# auto_gardener.net
KiCad netlist of a schematic drawn in EAGLE
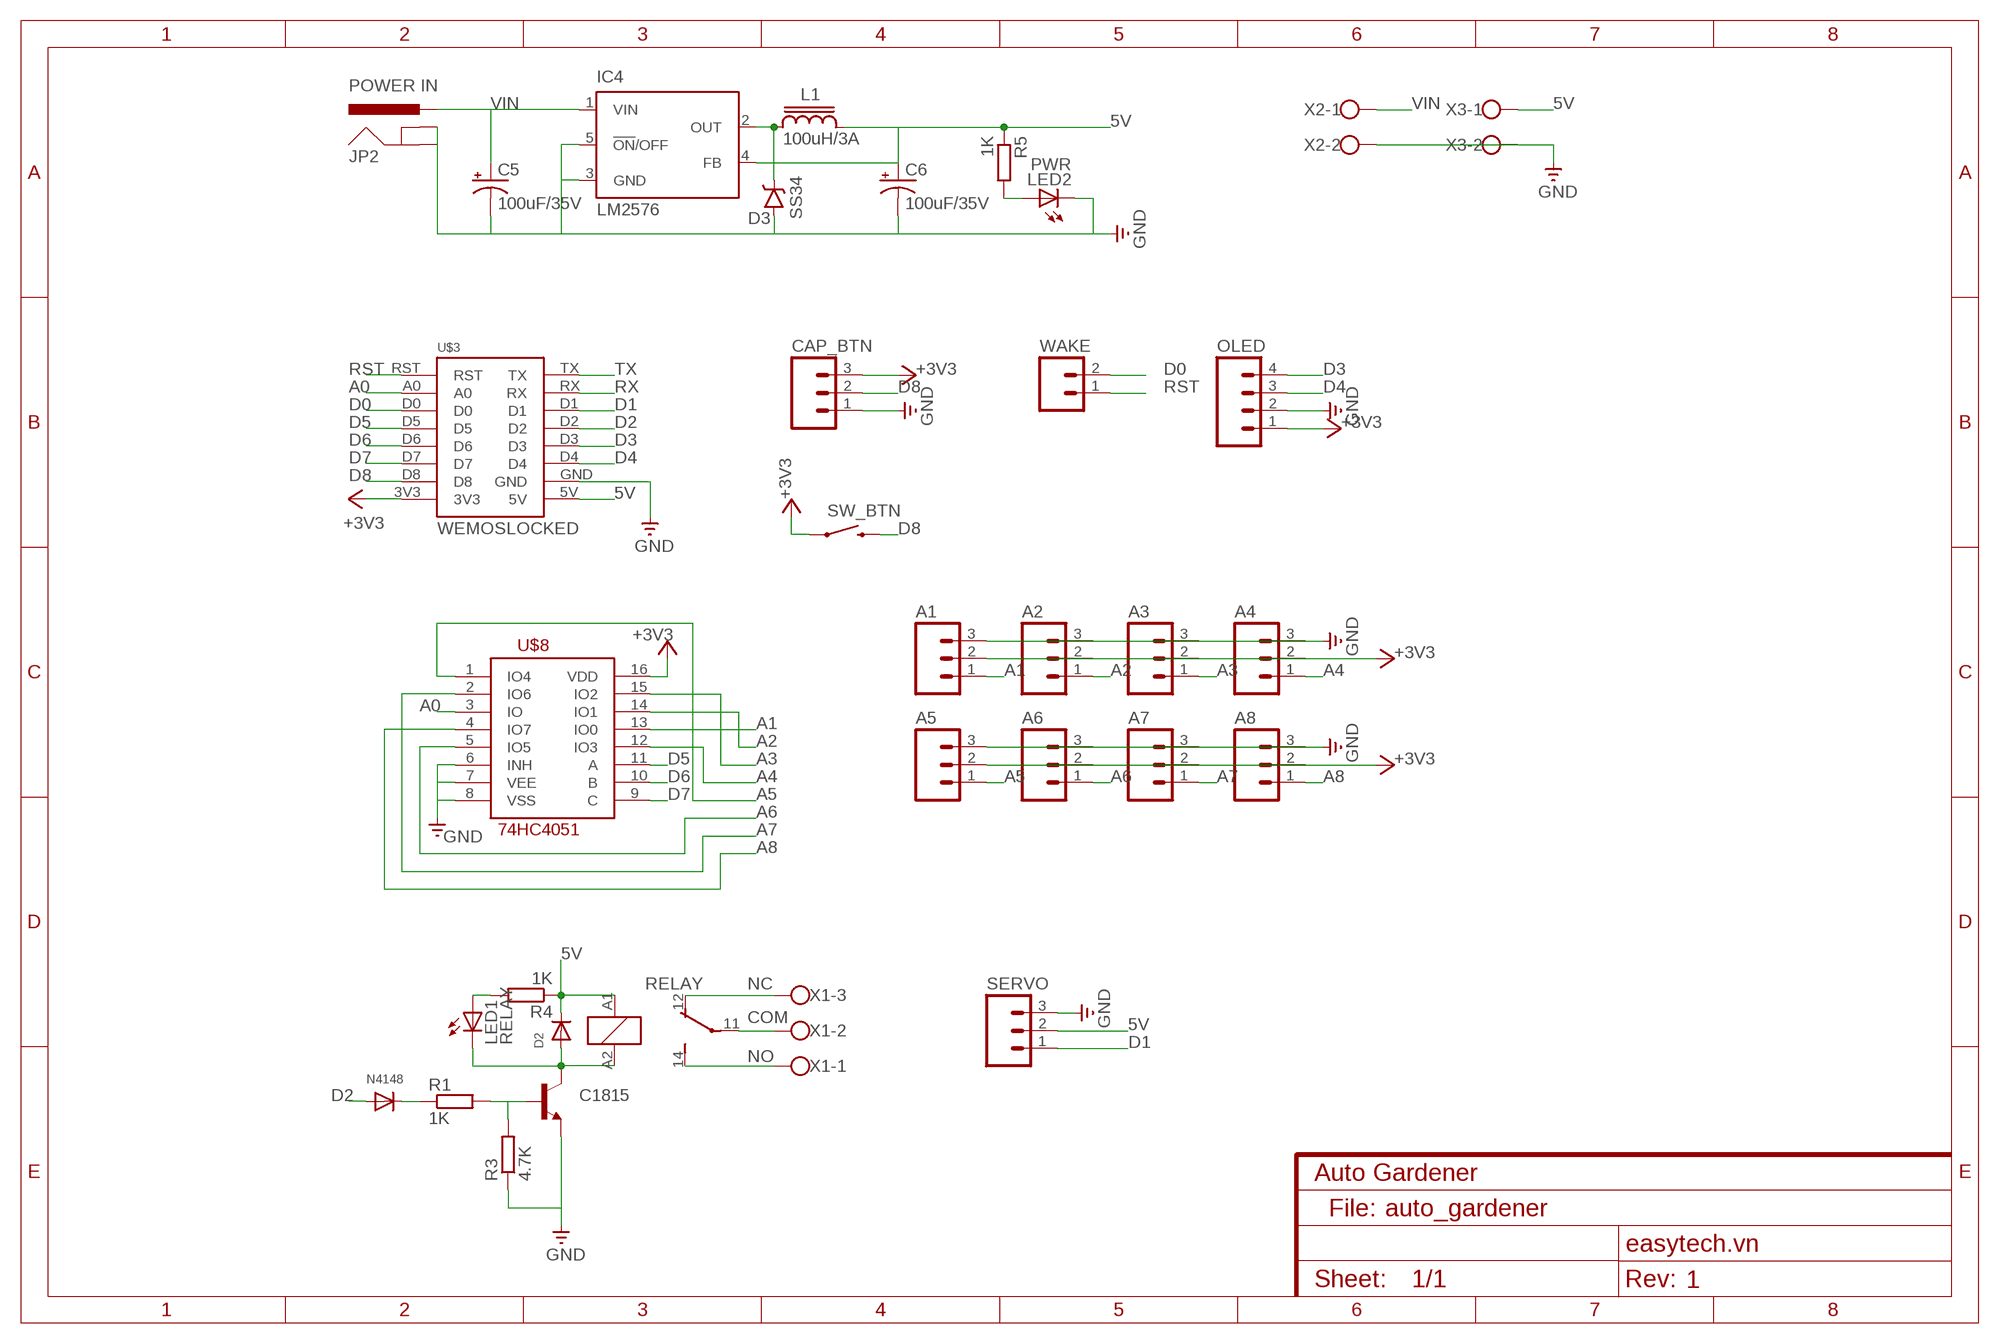
[diagram p0: schematic, sheet 1]

(export (version "E")
  (design (tool "Eeschema 10.0.6"))
  (components
    (comp (ref "A1")
      (value "M03PTH")
      (footprint "eagle-import:1X03")
      (libsource (lib "eagle-import") (part "M03PTH"))
    )
    (comp (ref "A2")
      (value "M03PTH")
      (footprint "eagle-import:1X03")
      (libsource (lib "eagle-import") (part "M03PTH"))
    )
    (comp (ref "A3")
      (value "M03PTH")
      (footprint "eagle-import:1X03")
      (libsource (lib "eagle-import") (part "M03PTH"))
    )
    (comp (ref "A4")
      (value "M03PTH")
      (footprint "eagle-import:1X03")
      (libsource (lib "eagle-import") (part "M03PTH"))
    )
    (comp (ref "A5")
      (value "M03PTH")
      (footprint "eagle-import:1X03")
      (libsource (lib "eagle-import") (part "M03PTH"))
    )
    (comp (ref "A6")
      (value "M03PTH")
      (footprint "eagle-import:1X03")
      (libsource (lib "eagle-import") (part "M03PTH"))
    )
    (comp (ref "A7")
      (value "M03PTH")
      (footprint "eagle-import:1X03")
      (libsource (lib "eagle-import") (part "M03PTH"))
    )
    (comp (ref "A8")
      (value "M03PTH")
      (footprint "eagle-import:1X03")
      (libsource (lib "eagle-import") (part "M03PTH"))
    )
    (comp (ref "C5")
      (value "100uF/35V")
      (footprint "eagle-import:PANASONIC_D")
      (libsource (lib "eagle-import") (part "CAP_POLD"))
    )
    (comp (ref "C6")
      (value "100uF/35V")
      (footprint "eagle-import:PANASONIC_D")
      (libsource (lib "eagle-import") (part "CAP_POLD"))
    )
    (comp (ref "C1815")
      (value "TRANSISTOR_NPNSOT23-3")
      (footprint "eagle-import:SOT23-3")
      (libsource (lib "eagle-import") (part "TRANSISTOR_NPNSOT23-3"))
    )
    (comp (ref "CAP_BTN")
      (value "M03PTH")
      (footprint "eagle-import:1X03")
      (libsource (lib "eagle-import") (part "M03PTH"))
    )
    (comp (ref "D2")
      (value "DIODESMA")
      (footprint "eagle-import:SMADIODE")
      (libsource (lib "eagle-import") (part "DIODESMA"))
    )
    (comp (ref "D3")
      (value "SS34")
      (footprint "eagle-import:SMA-DIODE")
      (libsource (lib "eagle-import") (part "MBRA140"))
    )
    (comp (ref "IC4")
      (value "LM2576")
      (footprint "eagle-import:TO263-5")
      (fields (field (name "MF") "NATIONAL SEMICONDUCTOR") (field (name "MPN") "LM2596S-ADJ/NOPB"))
      (libsource (lib "eagle-import") (part "LM2596S"))
    )
    (comp (ref "JP2")
      (value "POWER IN")
      (footprint "eagle-import:POWER_JACK_PTH")
      (libsource (lib "eagle-import") (part "POWER_JACKPTH"))
    )
    (comp (ref "L1")
      (value "100uH/3A")
      (footprint "eagle-import:CDRH127_LD")
      (libsource (lib "eagle-import") (part "CDRH127/LD"))
    )
    (comp (ref "LED1")
      (value "RELAY")
      (footprint "eagle-import:LED3MM")
      (libsource (lib "eagle-import") (part "LED3MM"))
    )
    (comp (ref "LED2")
      (value "PWR")
      (footprint "eagle-import:LED3MM")
      (libsource (lib "eagle-import") (part "LED3MM"))
    )
    (comp (ref "N4148")
      (value "DIODESOD-123")
      (footprint "eagle-import:SOD-123")
      (libsource (lib "eagle-import") (part "DIODESOD-123"))
    )
    (comp (ref "OLED")
      (value "M04PTH")
      (footprint "eagle-import:1X04")
      (libsource (lib "eagle-import") (part "M04PTH"))
    )
    (comp (ref "R1")
      (value "1K")
      (footprint "eagle-import:R0805")
      (libsource (lib "eagle-import") (part "R-EU_R0805"))
    )
    (comp (ref "R3")
      (value "4.7K")
      (footprint "eagle-import:R0805")
      (libsource (lib "eagle-import") (part "R-EU_R0805"))
    )
    (comp (ref "R4")
      (value "1K")
      (footprint "eagle-import:R0805")
      (libsource (lib "eagle-import") (part "R-EU_R0805"))
    )
    (comp (ref "R5")
      (value "1K")
      (footprint "eagle-import:R0805")
      (libsource (lib "eagle-import") (part "R-EU_R0805"))
    )
    (comp (ref "RELAY")
      (value "ZNS5106")
      (footprint "eagle-import:ZN5")
      (libsource (lib "eagle-import") (part "ZNS5106"))
    )
    (comp (ref "SERVO")
      (value "M03PTH")
      (footprint "eagle-import:1X03")
      (libsource (lib "eagle-import") (part "M03PTH"))
    )
    (comp (ref "SW_BTN")
      (value "SWITCH-MOMENTARY-212MM")
      (footprint "eagle-import:TACTILE-PTH-12MM")
      (libsource (lib "eagle-import") (part "SWITCH-MOMENTARY-212MM"))
    )
    (comp (ref "U$3")
      (value "WEMOSLOCKED")
      (footprint "eagle-import:WEMOS_LOCKED")
      (libsource (lib "eagle-import") (part "WEMOSLOCKED"))
    )
    (comp (ref "U$8")
      (value "74HC4051")
      (footprint "eagle-import:74HC4051")
      (libsource (lib "eagle-import") (part "74HC4051"))
    )
    (comp (ref "WAKE")
      (value "M02PTH")
      (footprint "eagle-import:1X02")
      (libsource (lib "eagle-import") (part "M02PTH"))
    )
    (comp (ref "X1")
      (value "W237-103")
      (footprint "eagle-import:W237-103")
      (fields (field (name "MPN") "237-103"))
      (libsource (lib "eagle-import") (part "W237-103"))
    )
    (comp (ref "X2")
      (value "W237-102")
      (footprint "eagle-import:W237-102")
      (fields (field (name "MPN") "237-102"))
      (libsource (lib "eagle-import") (part "W237-102"))
    )
    (comp (ref "X3")
      (value "W237-102")
      (footprint "eagle-import:W237-102")
      (fields (field (name "MPN") "237-102"))
      (libsource (lib "eagle-import") (part "W237-102"))
    )
  )
  (nets
    (net (code "1") (name "+3V3") (class "Default")
      (node (ref "A1") (pin "2") (pinfunction "2_2") (pintype "passive"))
      (node (ref "A2") (pin "2") (pinfunction "2_2") (pintype "passive"))
      (node (ref "A3") (pin "2") (pinfunction "2_2") (pintype "passive"))
      (node (ref "A4") (pin "2") (pinfunction "2_2") (pintype "passive"))
      (node (ref "A5") (pin "2") (pinfunction "2_2") (pintype "passive"))
      (node (ref "A6") (pin "2") (pinfunction "2_2") (pintype "passive"))
      (node (ref "A7") (pin "2") (pinfunction "2_2") (pintype "passive"))
      (node (ref "A8") (pin "2") (pinfunction "2_2") (pintype "passive"))
      (node (ref "CAP_BTN") (pin "3") (pinfunction "3_3") (pintype "passive"))
      (node (ref "OLED") (pin "1") (pinfunction "1_1") (pintype "passive"))
      (node (ref "SW_BTN") (pin "1") (pinfunction "1_1") (pintype "passive"))
      (node (ref "U$3") (pin "3V3") (pinfunction "3V3_3V3") (pintype "bidirectional"))
      (node (ref "U$8") (pin "16") (pinfunction "VDD_16") (pintype "bidirectional"))
    )
    (net (code "2") (name "/5V") (class "Default")
      (node (ref "C6") (pin "+") (pinfunction "+_+") (pintype "passive"))
      (node (ref "D2") (pin "C") (pinfunction "C_C") (pintype "passive"))
      (node (ref "IC4") (pin "4") (pinfunction "FB_4") (pintype "input"))
      (node (ref "L1") (pin "2") (pinfunction "2_2") (pintype "passive"))
      (node (ref "R4") (pin "1") (pinfunction "1_1") (pintype "passive"))
      (node (ref "R5") (pin "1") (pinfunction "1_1") (pintype "passive"))
      (node (ref "RELAY") (pin "A1") (pinfunction "1_A1") (pintype "passive"))
      (node (ref "SERVO") (pin "2") (pinfunction "2_2") (pintype "passive"))
      (node (ref "U$3") (pin "5V") (pinfunction "5V_5V") (pintype "bidirectional"))
      (node (ref "X3") (pin "1") (pinfunction "KL_1") (pintype "passive"))
    )
    (net (code "3") (name "/A0") (class "Default")
      (node (ref "U$3") (pin "A0") (pinfunction "A0_A0") (pintype "bidirectional"))
      (node (ref "U$8") (pin "3") (pinfunction "IO_3") (pintype "bidirectional"))
    )
    (net (code "4") (name "/A1") (class "Default")
      (node (ref "A1") (pin "1") (pinfunction "1_1") (pintype "passive"))
      (node (ref "U$8") (pin "13") (pinfunction "IO0_13") (pintype "bidirectional"))
    )
    (net (code "5") (name "/A2") (class "Default")
      (node (ref "A2") (pin "1") (pinfunction "1_1") (pintype "passive"))
      (node (ref "U$8") (pin "14") (pinfunction "IO1_14") (pintype "bidirectional"))
    )
    (net (code "6") (name "/A3") (class "Default")
      (node (ref "A3") (pin "1") (pinfunction "1_1") (pintype "passive"))
      (node (ref "U$8") (pin "15") (pinfunction "IO2_15") (pintype "bidirectional"))
    )
    (net (code "7") (name "/A4") (class "Default")
      (node (ref "A4") (pin "1") (pinfunction "1_1") (pintype "passive"))
      (node (ref "U$8") (pin "12") (pinfunction "IO3_12") (pintype "bidirectional"))
    )
    (net (code "8") (name "/A5") (class "Default")
      (node (ref "A5") (pin "1") (pinfunction "1_1") (pintype "passive"))
      (node (ref "U$8") (pin "1") (pinfunction "IO4_1") (pintype "bidirectional"))
    )
    (net (code "9") (name "/A6") (class "Default")
      (node (ref "A6") (pin "1") (pinfunction "1_1") (pintype "passive"))
      (node (ref "U$8") (pin "5") (pinfunction "IO5_5") (pintype "bidirectional"))
    )
    (net (code "10") (name "/A7") (class "Default")
      (node (ref "A7") (pin "1") (pinfunction "1_1") (pintype "passive"))
      (node (ref "U$8") (pin "2") (pinfunction "IO6_2") (pintype "bidirectional"))
    )
    (net (code "11") (name "/A8") (class "Default")
      (node (ref "A8") (pin "1") (pinfunction "1_1") (pintype "passive"))
      (node (ref "U$8") (pin "4") (pinfunction "IO7_4") (pintype "bidirectional"))
    )
    (net (code "12") (name "/COM") (class "Default")
      (node (ref "RELAY") (pin "11") (pinfunction "P_11") (pintype "passive"))
      (node (ref "X1") (pin "2") (pinfunction "KL_2") (pintype "passive"))
    )
    (net (code "13") (name "/D0") (class "Default")
      (node (ref "U$3") (pin "D0") (pinfunction "D0_D0") (pintype "bidirectional"))
      (node (ref "WAKE") (pin "2") (pinfunction "2_2") (pintype "passive"))
    )
    (net (code "14") (name "/D1") (class "Default")
      (node (ref "SERVO") (pin "1") (pinfunction "1_1") (pintype "passive"))
      (node (ref "U$3") (pin "D1") (pinfunction "D1_D1") (pintype "bidirectional"))
    )
    (net (code "15") (name "/D2") (class "Default")
      (node (ref "N4148") (pin "A") (pinfunction "A_A") (pintype "passive"))
      (node (ref "U$3") (pin "D2") (pinfunction "D2_D2") (pintype "bidirectional"))
    )
    (net (code "16") (name "/D3") (class "Default")
      (node (ref "OLED") (pin "4") (pinfunction "4_4") (pintype "passive"))
      (node (ref "U$3") (pin "D3") (pinfunction "D3_D3") (pintype "bidirectional"))
    )
    (net (code "17") (name "/D4") (class "Default")
      (node (ref "OLED") (pin "3") (pinfunction "3_3") (pintype "passive"))
      (node (ref "U$3") (pin "D4") (pinfunction "D4_D4") (pintype "bidirectional"))
    )
    (net (code "18") (name "/D5") (class "Default")
      (node (ref "U$3") (pin "D5") (pinfunction "D5_D5") (pintype "bidirectional"))
      (node (ref "U$8") (pin "11") (pinfunction "A_11") (pintype "bidirectional"))
    )
    (net (code "19") (name "/D6") (class "Default")
      (node (ref "U$3") (pin "D6") (pinfunction "D6_D6") (pintype "bidirectional"))
      (node (ref "U$8") (pin "10") (pinfunction "B_10") (pintype "bidirectional"))
    )
    (net (code "20") (name "/D7") (class "Default")
      (node (ref "U$3") (pin "D7") (pinfunction "D7_D7") (pintype "bidirectional"))
      (node (ref "U$8") (pin "9") (pinfunction "C_9") (pintype "bidirectional"))
    )
    (net (code "21") (name "/D8") (class "Default")
      (node (ref "CAP_BTN") (pin "2") (pinfunction "2_2") (pintype "passive"))
      (node (ref "SW_BTN") (pin "3") (pinfunction "2_3") (pintype "passive"))
      (node (ref "U$3") (pin "D8") (pinfunction "D8_D8") (pintype "bidirectional"))
    )
    (net (code "22") (name "/NC") (class "Default")
      (node (ref "RELAY") (pin "12") (pinfunction "O_12") (pintype "passive"))
      (node (ref "X1") (pin "3") (pinfunction "KL_3") (pintype "passive"))
    )
    (net (code "23") (name "/NO") (class "Default")
      (node (ref "RELAY") (pin "14") (pinfunction "S_14") (pintype "passive"))
      (node (ref "X1") (pin "1") (pinfunction "KL_1") (pintype "passive"))
    )
    (net (code "24") (name "/RST") (class "Default")
      (node (ref "U$3") (pin "RST") (pinfunction "RST_RST") (pintype "bidirectional"))
      (node (ref "WAKE") (pin "1") (pinfunction "1_1") (pintype "passive"))
    )
    (net (code "25") (name "/RX") (class "Default")
      (node (ref "U$3") (pin "RX") (pinfunction "RX_RX") (pintype "bidirectional"))
    )
    (net (code "26") (name "/TX") (class "Default")
      (node (ref "U$3") (pin "TX") (pinfunction "TX_TX") (pintype "bidirectional"))
    )
    (net (code "27") (name "/VIN") (class "Default")
      (node (ref "C5") (pin "+") (pinfunction "+_+") (pintype "passive"))
      (node (ref "IC4") (pin "1") (pinfunction "VIN_1") (pintype "input"))
      (node (ref "JP2") (pin "PWR") (pinfunction "PWR_PWR") (pintype "bidirectional"))
      (node (ref "X2") (pin "1") (pinfunction "KL_1") (pintype "passive"))
    )
    (net (code "28") (name "GND") (class "Default")
      (node (ref "A1") (pin "3") (pinfunction "3_3") (pintype "passive"))
      (node (ref "A2") (pin "3") (pinfunction "3_3") (pintype "passive"))
      (node (ref "A3") (pin "3") (pinfunction "3_3") (pintype "passive"))
      (node (ref "A4") (pin "3") (pinfunction "3_3") (pintype "passive"))
      (node (ref "A5") (pin "3") (pinfunction "3_3") (pintype "passive"))
      (node (ref "A6") (pin "3") (pinfunction "3_3") (pintype "passive"))
      (node (ref "A7") (pin "3") (pinfunction "3_3") (pintype "passive"))
      (node (ref "A8") (pin "3") (pinfunction "3_3") (pintype "passive"))
      (node (ref "C1815") (pin "2") (pinfunction "E_2") (pintype "passive"))
      (node (ref "C5") (pin "-") (pinfunction "-_-") (pintype "passive"))
      (node (ref "C6") (pin "-") (pinfunction "-_-") (pintype "passive"))
      (node (ref "CAP_BTN") (pin "1") (pinfunction "1_1") (pintype "passive"))
      (node (ref "D3") (pin "A") (pinfunction "A_A") (pintype "passive"))
      (node (ref "IC4") (pin "3") (pinfunction "GND_3") (pintype "power_in"))
      (node (ref "IC4") (pin "5") (pinfunction "~{ON}/OFF_5") (pintype "input"))
      (node (ref "JP2") (pin "GND") (pinfunction "GND_GND") (pintype "bidirectional"))
      (node (ref "JP2") (pin "GNDBREAK") (pinfunction "GNDBREAK_GNDBREAK") (pintype "bidirectional"))
      (node (ref "LED2") (pin "K") (pinfunction "C_K") (pintype "passive"))
      (node (ref "OLED") (pin "2") (pinfunction "2_2") (pintype "passive"))
      (node (ref "R3") (pin "1") (pinfunction "1_1") (pintype "passive"))
      (node (ref "SERVO") (pin "3") (pinfunction "3_3") (pintype "passive"))
      (node (ref "U$3") (pin "GND") (pinfunction "GND_GND") (pintype "bidirectional"))
      (node (ref "U$8") (pin "6") (pinfunction "INH_6") (pintype "bidirectional"))
      (node (ref "U$8") (pin "7") (pinfunction "VEE_7") (pintype "bidirectional"))
      (node (ref "U$8") (pin "8") (pinfunction "VSS_8") (pintype "bidirectional"))
      (node (ref "X2") (pin "2") (pinfunction "KL_2") (pintype "passive"))
      (node (ref "X3") (pin "2") (pinfunction "KL_2") (pintype "passive"))
    )
    (net (code "29") (name "Net-(C1815-B)") (class "Default")
      (node (ref "C1815") (pin "1") (pinfunction "B_1") (pintype "passive"))
      (node (ref "R1") (pin "2") (pinfunction "2_2") (pintype "passive"))
      (node (ref "R3") (pin "2") (pinfunction "2_2") (pintype "passive"))
    )
    (net (code "30") (name "Net-(C1815-C)") (class "Default")
      (node (ref "C1815") (pin "3") (pinfunction "C_3") (pintype "passive"))
      (node (ref "D2") (pin "A") (pinfunction "A_A") (pintype "passive"))
      (node (ref "LED1") (pin "K") (pinfunction "C_K") (pintype "passive"))
      (node (ref "RELAY") (pin "A2") (pinfunction "2_A2") (pintype "passive"))
    )
    (net (code "31") (name "Net-(IC4-OUT)") (class "Default")
      (node (ref "D3") (pin "C") (pinfunction "C_C") (pintype "passive"))
      (node (ref "IC4") (pin "2") (pinfunction "OUT_2") (pintype "output"))
      (node (ref "L1") (pin "1") (pinfunction "1_1") (pintype "passive"))
    )
    (net (code "32") (name "Net-(LED1-PadA)") (class "Default")
      (node (ref "LED1") (pin "A") (pinfunction "A_A") (pintype "passive"))
      (node (ref "R4") (pin "2") (pinfunction "2_2") (pintype "passive"))
    )
    (net (code "33") (name "Net-(LED2-PadA)") (class "Default")
      (node (ref "LED2") (pin "A") (pinfunction "A_A") (pintype "passive"))
      (node (ref "R5") (pin "2") (pinfunction "2_2") (pintype "passive"))
    )
    (net (code "34") (name "Net-(N4148-PadC)") (class "Default")
      (node (ref "N4148") (pin "C") (pinfunction "C_C") (pintype "passive"))
      (node (ref "R1") (pin "1") (pinfunction "1_1") (pintype "passive"))
    )
  )
)
